# 464342_21-005_3_4.net
KiCad netlist of a schematic drawn in Altium Designer
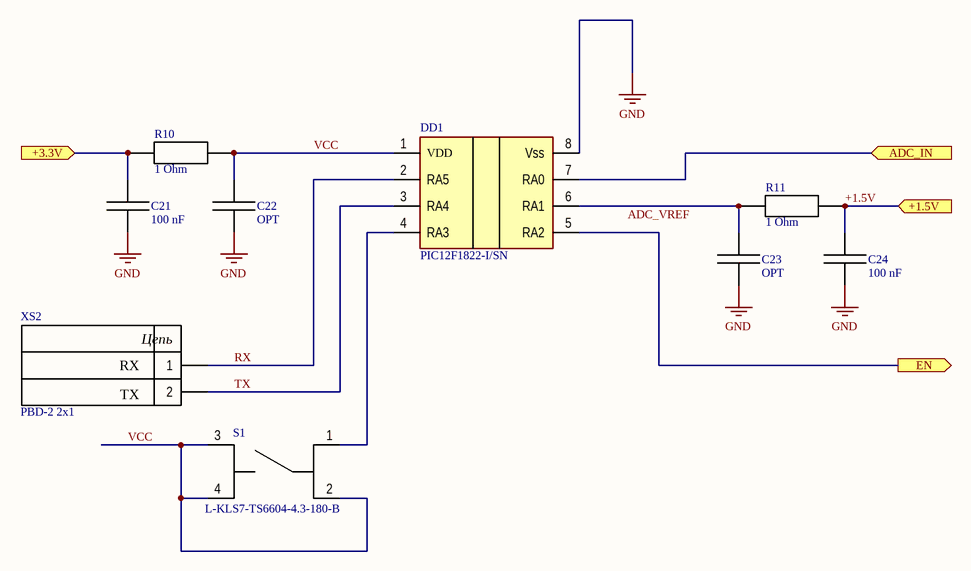
[diagram p0: МПСУ.464342.21-005 Э3 Лист4.SchDoc]

(export (version "E")
  (design (tool "Eeschema 10.0.6"))
  (components
    (comp (ref "C21")
      (value "100 nF")
      (footprint "CAPC100X50X55L20N")
      (description "Capacitor, generic")
      (libsource (lib "Discrete") (part "Capacitor"))
    )
    (comp (ref "C22")
      (value "OPT")
      (footprint "CAPC100X50X55L20N")
      (description "Capacitor, generic")
      (libsource (lib "Discrete") (part "Capacitor"))
    )
    (comp (ref "C23")
      (value "OPT")
      (footprint "CAPC100X50X55L20N")
      (description "Capacitor, generic")
      (libsource (lib "Discrete") (part "Capacitor"))
    )
    (comp (ref "C24")
      (value "100 nF")
      (footprint "CAPC100X50X55L20N")
      (description "Capacitor, generic")
      (libsource (lib "Discrete") (part "Capacitor"))
    )
    (comp (ref "DD1")
      (value "PIC12F1822-I/SN")
      (footprint "SN-SOIC127P600X175-8N")
      (description "8-bit Flash Microcontrollers with XLP Technology 3.5 KB, 128 B")
      (libsource (lib "IC") (part "PIC12(L)F1822"))
    )
    (comp (ref "R10")
      (value "1 Ohm")
      (footprint "RESC100X50X40L25N")
      (description "Resistor, generic")
      (libsource (lib "Discrete") (part "Resistor"))
    )
    (comp (ref "R11")
      (value "1 Ohm")
      (footprint "RESC100X50X40L25N")
      (description "Resistor, generic")
      (libsource (lib "") (part "Resistor_1"))
    )
    (comp (ref "S1")
      (value "L-KLS7-TS6604-4.3-180-B")
      (footprint "DIP2_SOIC450P1000X350-4N")
      (description "Tact Switch")
      (fields (field (name "MANUFACTURER") "KLS electronic co ltd"))
      (libsource (lib "SWITCHES") (part "KLS7-TS6601-7"))
    )
    (comp (ref "XS2")
      (value "PBD-2 2x1")
      (footprint "RHDRV2W45P254_1X2_304X500H500")
      (description "Header, Vertical Receptacle, 2.54 mm pitch 2x1")
      (libsource (lib "Connectors") (part "PBD-2"))
    )
  )
  (nets
    (net (code "1") (name "/+1.5V") (class "Default")
      (node (ref "C24") (pin "2") (pinfunction "2_2") (pintype "passive"))
      (node (ref "R11") (pin "2") (pinfunction "2_2") (pintype "passive"))
    )
    (net (code "2") (name "/+3.3V") (class "Default")
      (node (ref "C21") (pin "2") (pinfunction "2_2") (pintype "passive"))
      (node (ref "R10") (pin "2") (pinfunction "2_2") (pintype "passive"))
    )
    (net (code "3") (name "/ADC_IN") (class "Default")
      (node (ref "DD1") (pin "7") (pinfunction "RA0_7") (pintype "passive"))
    )
    (net (code "4") (name "/ADC_VREF") (class "Default")
      (node (ref "C23") (pin "2") (pinfunction "2_2") (pintype "passive"))
      (node (ref "DD1") (pin "6") (pinfunction "RA1_6") (pintype "passive"))
      (node (ref "R11") (pin "1") (pinfunction "1_1") (pintype "passive"))
    )
    (net (code "5") (name "/EN") (class "Default")
      (node (ref "DD1") (pin "5") (pinfunction "RA2_5") (pintype "passive"))
    )
    (net (code "6") (name "/RX") (class "Default")
      (node (ref "DD1") (pin "2") (pinfunction "RA5_2") (pintype "passive"))
      (node (ref "XS2") (pin "1") (pinfunction "1_1") (pintype "passive"))
    )
    (net (code "7") (name "/TX") (class "Default")
      (node (ref "DD1") (pin "3") (pinfunction "RA4_3") (pintype "passive"))
      (node (ref "XS2") (pin "2") (pinfunction "2_2") (pintype "passive"))
    )
    (net (code "8") (name "/VCC") (class "Default")
      (node (ref "C22") (pin "2") (pinfunction "2_2") (pintype "passive"))
      (node (ref "DD1") (pin "1") (pinfunction "VDD_1") (pintype "passive"))
      (node (ref "R10") (pin "1") (pinfunction "1_1") (pintype "passive"))
      (node (ref "S1") (pin "2") (pinfunction "2_2") (pintype "passive"))
      (node (ref "S1") (pin "3") (pinfunction "3_3") (pintype "passive"))
      (node (ref "S1") (pin "4") (pinfunction "4_4") (pintype "passive"))
    )
    (net (code "9") (name "GND") (class "Default")
      (node (ref "C21") (pin "1") (pinfunction "1_1") (pintype "passive"))
      (node (ref "C22") (pin "1") (pinfunction "1_1") (pintype "passive"))
      (node (ref "C23") (pin "1") (pinfunction "1_1") (pintype "passive"))
      (node (ref "C24") (pin "1") (pinfunction "1_1") (pintype "passive"))
      (node (ref "DD1") (pin "8") (pinfunction "Vss_8") (pintype "passive"))
    )
    (net (code "10") (name "Net-(DD1-RA3)") (class "Default")
      (node (ref "DD1") (pin "4") (pinfunction "RA3_4") (pintype "passive"))
      (node (ref "S1") (pin "1") (pinfunction "1_1") (pintype "passive"))
    )
  )
)
